# MPU9250-.net
KiCad netlist of a schematic drawn in Altium Designer
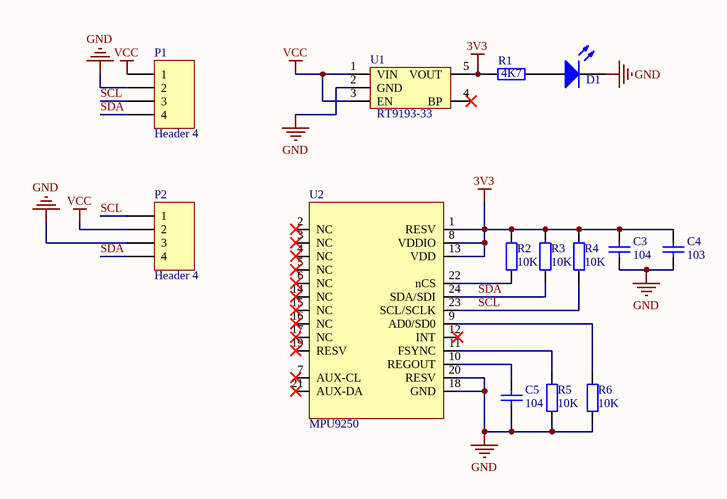
[diagram p0: MPU9250-原理图.SchDoc]

(export (version "E")
  (design (tool "Eeschema 10.0.6"))
  (components
    (comp (ref "C3")
      (value "104")
      (footprint "1__0402-CAP(有丝印)")
      (description "Capacitor")
      (libsource (lib "Miscellaneous Devices") (part "Cap"))
    )
    (comp (ref "C4")
      (value "103")
      (footprint "1__0402-CAP(有丝印)")
      (description "Capacitor")
      (libsource (lib "Miscellaneous Devices") (part "Cap"))
    )
    (comp (ref "C5")
      (value "104")
      (footprint "1__0402-CAP(有丝印)")
      (description "Capacitor")
      (libsource (lib "Miscellaneous Devices") (part "Cap"))
    )
    (comp (ref "D1")
      (value "LED")
      (footprint "1__0603-LED_")
      (description "Typical INFRARED GaAs LED")
      (libsource (lib "Miscellaneous Devices") (part "LED0"))
    )
    (comp (ref "P1")
      (value "Header 4")
      (footprint "1__排针_贴片单_4P两侧")
      (description "Header, 4-Pin")
      (fields (field (name "PUBLISHER") "Altium Limited"))
      (libsource (lib "!)Miscellaneous Integrated Library") (part "Header 4"))
    )
    (comp (ref "P2")
      (value "Header 4")
      (footprint "1__FPC 4P (临时用)")
      (description "Header, 4-Pin")
      (fields (field (name "PUBLISHER") "Altium Limited"))
      (libsource (lib "!)Miscellaneous Integrated Library") (part "Header 4"))
    )
    (comp (ref "R1")
      (value "4K7")
      (footprint "1__0402-RES(有丝印)")
      (description "Resistor")
      (libsource (lib "") (part "Res2_1"))
    )
    (comp (ref "R2")
      (value "10K")
      (footprint "1__0402-RES(有丝印)")
      (description "Resistor")
      (libsource (lib "Miscellaneous Devices") (part "Res2"))
    )
    (comp (ref "R3")
      (value "10K")
      (footprint "1__0402-RES(有丝印)")
      (description "Resistor")
      (libsource (lib "Miscellaneous Devices") (part "Res2"))
    )
    (comp (ref "R4")
      (value "10K")
      (footprint "1__0402-RES(有丝印)")
      (description "Resistor")
      (libsource (lib "Miscellaneous Devices") (part "Res2"))
    )
    (comp (ref "R5")
      (value "10K")
      (footprint "1__0402-RES(有丝印)")
      (description "Resistor")
      (libsource (lib "Miscellaneous Devices") (part "Res2"))
    )
    (comp (ref "R6")
      (value "10K")
      (footprint "1__0402-RES(有丝印)")
      (description "Resistor")
      (libsource (lib "Miscellaneous Devices") (part "Res2"))
    )
    (comp (ref "U1")
      (value "RT9193-33")
      (footprint "1__SOT23-5")
      (description "3.3V超低压差LDO")
      (libsource (lib "MPU6050") (part "RT9193-33"))
    )
    (comp (ref "U2")
      (value "MPU9250")
      (footprint "1__QFN3*3 (改)")
      (libsource (lib "Schlib1") (part "MPU9250"))
    )
  )
  (nets
    (net (code "1") (name "/SCL") (class "Default")
      (node (ref "P1") (pin "3") (pinfunction "3_3") (pintype "passive"))
      (node (ref "P2") (pin "1") (pinfunction "1_1") (pintype "passive"))
      (node (ref "R4") (pin "1") (pinfunction "1_1") (pintype "passive"))
      (node (ref "U2") (pin "23") (pinfunction "SCL/SCLK_23") (pintype "passive"))
    )
    (net (code "2") (name "/SDA") (class "Default")
      (node (ref "P1") (pin "4") (pinfunction "4_4") (pintype "passive"))
      (node (ref "P2") (pin "4") (pinfunction "4_4") (pintype "passive"))
      (node (ref "R3") (pin "1") (pinfunction "1_1") (pintype "passive"))
      (node (ref "U2") (pin "24") (pinfunction "SDA/SDI_24") (pintype "passive"))
    )
    (net (code "3") (name "3V3") (class "Default")
      (node (ref "C3") (pin "2") (pinfunction "2_2") (pintype "passive"))
      (node (ref "C4") (pin "2") (pinfunction "2_2") (pintype "passive"))
      (node (ref "R1") (pin "1") (pinfunction "1_1") (pintype "passive"))
      (node (ref "R2") (pin "2") (pinfunction "2_2") (pintype "passive"))
      (node (ref "R3") (pin "2") (pinfunction "2_2") (pintype "passive"))
      (node (ref "R4") (pin "2") (pinfunction "2_2") (pintype "passive"))
      (node (ref "U1") (pin "5") (pinfunction "VOUT_5") (pintype "passive"))
      (node (ref "U2") (pin "1") (pinfunction "RESV_1") (pintype "passive"))
      (node (ref "U2") (pin "13") (pinfunction "VDD_13") (pintype "passive"))
      (node (ref "U2") (pin "8") (pinfunction "VDDIO_8") (pintype "passive"))
    )
    (net (code "4") (name "GND") (class "Default")
      (node (ref "C3") (pin "1") (pinfunction "1_1") (pintype "passive"))
      (node (ref "C4") (pin "1") (pinfunction "1_1") (pintype "passive"))
      (node (ref "C5") (pin "1") (pinfunction "1_1") (pintype "passive"))
      (node (ref "D1") (pin "2") (pinfunction "2_2") (pintype "passive"))
      (node (ref "P1") (pin "2") (pinfunction "2_2") (pintype "passive"))
      (node (ref "P2") (pin "3") (pinfunction "3_3") (pintype "passive"))
      (node (ref "R5") (pin "1") (pinfunction "1_1") (pintype "passive"))
      (node (ref "R6") (pin "1") (pinfunction "1_1") (pintype "passive"))
      (node (ref "U1") (pin "2") (pinfunction "GND_2") (pintype "passive"))
      (node (ref "U2") (pin "18") (pinfunction "GND_18") (pintype "passive"))
      (node (ref "U2") (pin "20") (pinfunction "RESV_20") (pintype "passive"))
    )
    (net (code "5") (name "Net-(D1-Pad1)") (class "Default")
      (node (ref "D1") (pin "1") (pinfunction "1_1") (pintype "passive"))
      (node (ref "R1") (pin "2") (pinfunction "2_2") (pintype "passive"))
    )
    (net (code "6") (name "Net-(U2-AD0{slash}SD0)") (class "Default")
      (node (ref "R6") (pin "2") (pinfunction "2_2") (pintype "passive"))
      (node (ref "U2") (pin "9") (pinfunction "AD0/SD0_9") (pintype "passive"))
    )
    (net (code "7") (name "Net-(U2-FSYNC)") (class "Default")
      (node (ref "R5") (pin "2") (pinfunction "2_2") (pintype "passive"))
      (node (ref "U2") (pin "11") (pinfunction "FSYNC_11") (pintype "passive"))
    )
    (net (code "8") (name "Net-(U2-REGOUT)") (class "Default")
      (node (ref "C5") (pin "2") (pinfunction "2_2") (pintype "passive"))
      (node (ref "U2") (pin "10") (pinfunction "REGOUT_10") (pintype "passive"))
    )
    (net (code "9") (name "Net-(U2-nCS)") (class "Default")
      (node (ref "R2") (pin "1") (pinfunction "1_1") (pintype "passive"))
      (node (ref "U2") (pin "22") (pinfunction "nCS_22") (pintype "passive"))
    )
    (net (code "10") (name "VCC") (class "Default")
      (node (ref "P1") (pin "1") (pinfunction "1_1") (pintype "passive"))
      (node (ref "P2") (pin "2") (pinfunction "2_2") (pintype "passive"))
      (node (ref "U1") (pin "1") (pinfunction "VIN_1") (pintype "passive"))
      (node (ref "U1") (pin "3") (pinfunction "EN_3") (pintype "passive"))
    )
    (net (code "11") (name "unconnected-(U1-BP-Pad4)") (class "Default")
      (node (ref "U1") (pin "4") (pinfunction "BP_4") (pintype "passive+no_connect"))
    )
    (net (code "12") (name "unconnected-(U2-AUX-CL-Pad7)") (class "Default")
      (node (ref "U2") (pin "7") (pinfunction "AUX-CL_7") (pintype "passive+no_connect"))
    )
    (net (code "13") (name "unconnected-(U2-AUX-DA-Pad21)") (class "Default")
      (node (ref "U2") (pin "21") (pinfunction "AUX-DA_21") (pintype "passive+no_connect"))
    )
    (net (code "14") (name "unconnected-(U2-INT-Pad12)") (class "Default")
      (node (ref "U2") (pin "12") (pinfunction "INT_12") (pintype "passive+no_connect"))
    )
    (net (code "15") (name "unconnected-(U2-NC-Pad2)") (class "Default")
      (node (ref "U2") (pin "2") (pinfunction "NC_2") (pintype "passive+no_connect"))
    )
    (net (code "16") (name "unconnected-(U2-NC-Pad3)") (class "Default")
      (node (ref "U2") (pin "3") (pinfunction "NC_3") (pintype "passive+no_connect"))
    )
    (net (code "17") (name "unconnected-(U2-NC-Pad4)") (class "Default")
      (node (ref "U2") (pin "4") (pinfunction "NC_4") (pintype "passive+no_connect"))
    )
    (net (code "18") (name "unconnected-(U2-NC-Pad5)") (class "Default")
      (node (ref "U2") (pin "5") (pinfunction "NC_5") (pintype "passive+no_connect"))
    )
    (net (code "19") (name "unconnected-(U2-NC-Pad6)") (class "Default")
      (node (ref "U2") (pin "6") (pinfunction "NC_6") (pintype "passive+no_connect"))
    )
    (net (code "20") (name "unconnected-(U2-NC-Pad14)") (class "Default")
      (node (ref "U2") (pin "14") (pinfunction "NC_14") (pintype "passive+no_connect"))
    )
    (net (code "21") (name "unconnected-(U2-NC-Pad15)") (class "Default")
      (node (ref "U2") (pin "15") (pinfunction "NC_15") (pintype "passive+no_connect"))
    )
    (net (code "22") (name "unconnected-(U2-NC-Pad16)") (class "Default")
      (node (ref "U2") (pin "16") (pinfunction "NC_16") (pintype "passive+no_connect"))
    )
    (net (code "23") (name "unconnected-(U2-NC-Pad17)") (class "Default")
      (node (ref "U2") (pin "17") (pinfunction "NC_17") (pintype "passive+no_connect"))
    )
    (net (code "24") (name "unconnected-(U2-RESV-Pad19)") (class "Default")
      (node (ref "U2") (pin "19") (pinfunction "RESV_19") (pintype "passive+no_connect"))
    )
  )
)
